# tcc-esquemaico-aplicacoes.net
KiCad netlist of a schematic drawn in EasyEDA
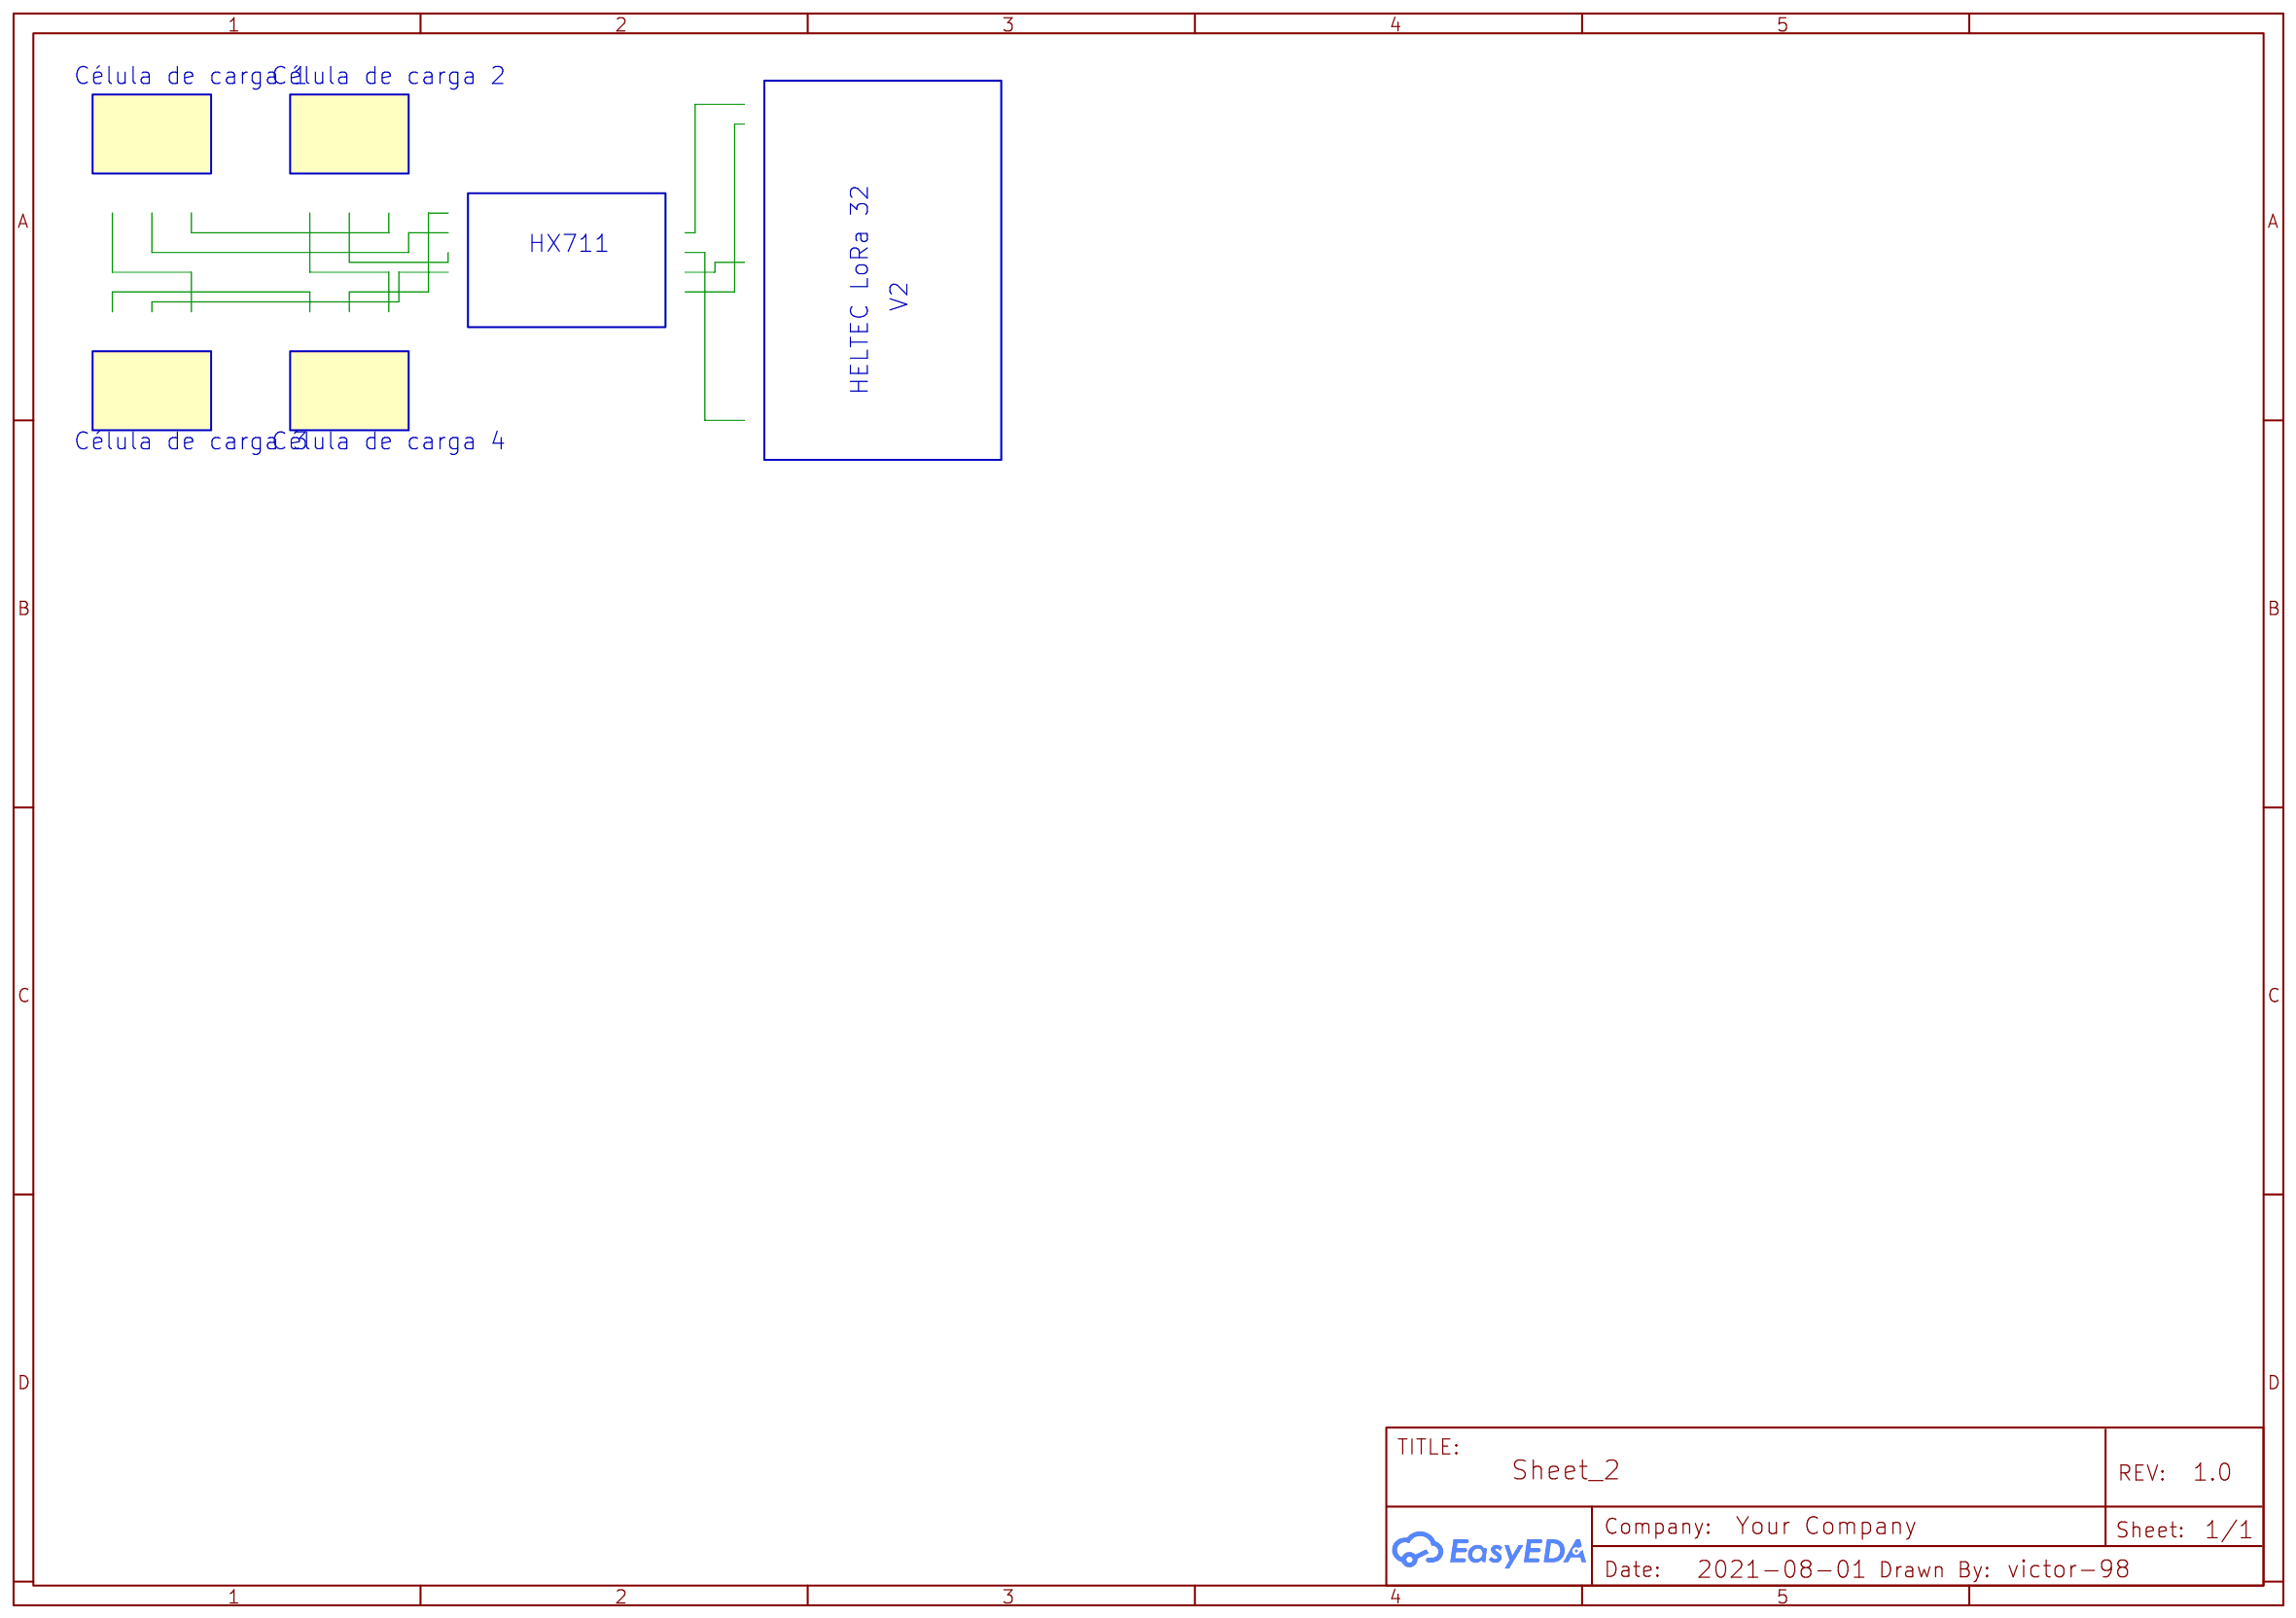
[diagram p0: balanca-tcc]
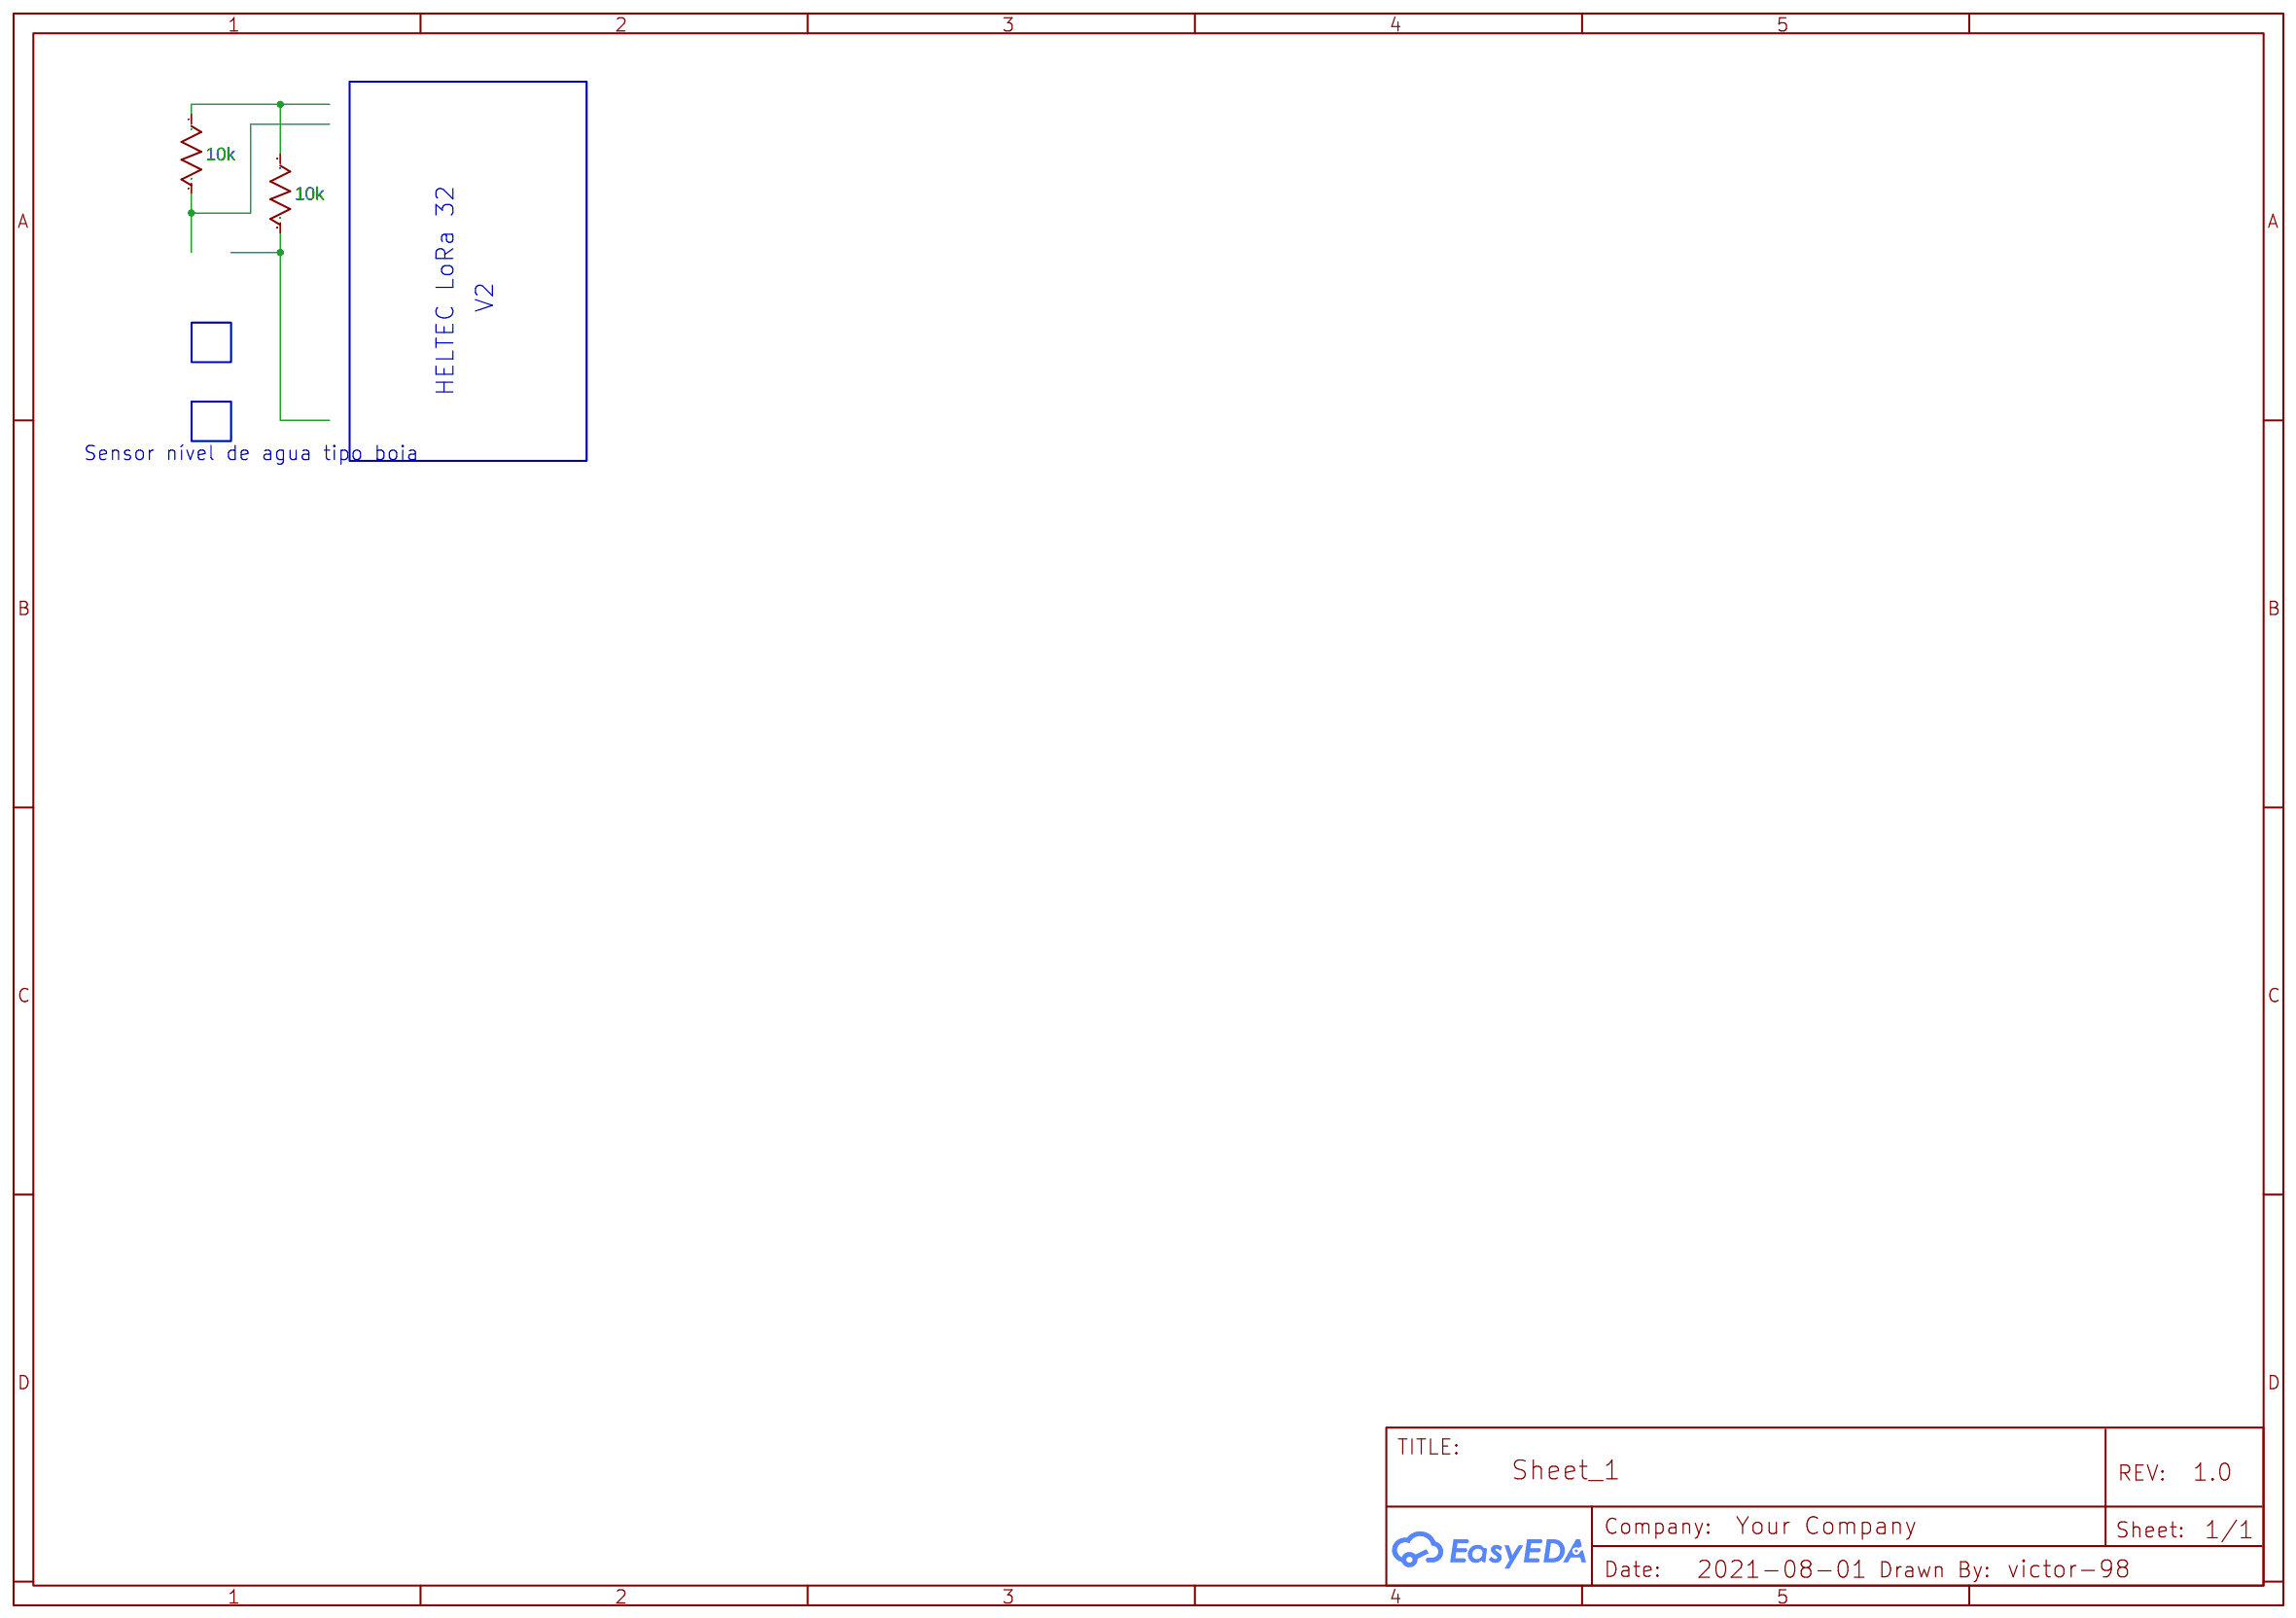
[diagram p1: nivel-agua-tcc]

(export (version "E")
  (design (tool "Eeschema 10.0.6"))
  (components
    (comp (ref "R1") (value "10k") (libsource (lib "") (part "R_0603_US")))
    (comp (ref "R2") (value "10k") (libsource (lib "") (part "R_0603_US")))
  )
  (nets
    (net (code "1") (name "Net-(R1-Pad1)") (class "Default")
      (node (ref "R1") (pin "1") (pinfunction "1_1") (pintype "unspecified"))
      (node (ref "R2") (pin "1") (pinfunction "1_1") (pintype "unspecified"))
    )
    (net (code "2") (name "unconnected-(R1-Pad2)") (class "Default")
      (node (ref "R1") (pin "2") (pinfunction "2_2") (pintype "unspecified"))
    )
    (net (code "3") (name "unconnected-(R2-Pad2)") (class "Default")
      (node (ref "R2") (pin "2") (pinfunction "2_2") (pintype "unspecified"))
    )
  )
)
